# nor.net
KiCad netlist of a schematic drawn in EAGLE
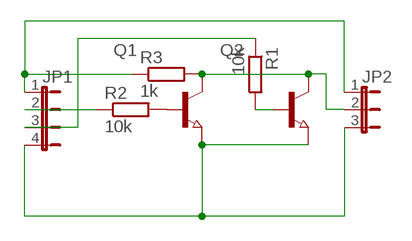
[diagram p0: schematic, sheet 1]

(export (version "E")
  (design (tool "Eeschema 10.0.6"))
  (components
    (comp (ref "JP1")
      (value "JP4E")
      (footprint "eagle-import:JP4")
      (libsource (lib "eagle-import") (part "JP4E"))
    )
    (comp (ref "JP2")
      (value "JP2W")
      (footprint "eagle-import:JP2W")
      (libsource (lib "eagle-import") (part "JP2W"))
    )
    (comp (ref "Q1")
      (value "NPN-TRANSISTOR_SOT23")
      (footprint "eagle-import:SOT23")
      (libsource (lib "eagle-import") (part "NPN-TRANSISTOR_SOT23"))
    )
    (comp (ref "Q2")
      (value "NPN-TRANSISTOR_SOT23")
      (footprint "eagle-import:SOT23")
      (libsource (lib "eagle-import") (part "NPN-TRANSISTOR_SOT23"))
    )
    (comp (ref "R1")
      (value "10k")
      (footprint "eagle-import:R1206")
      (libsource (lib "eagle-import") (part "R-EU_R1206"))
    )
    (comp (ref "R2")
      (value "10k")
      (footprint "eagle-import:R1206")
      (libsource (lib "eagle-import") (part "R-EU_R1206"))
    )
    (comp (ref "R3")
      (value "1k")
      (footprint "eagle-import:R1206")
      (libsource (lib "eagle-import") (part "R-EU_R1206"))
    )
  )
  (nets
    (net (code "1") (name "Net-(JP1-Pad1)") (class "Default")
      (node (ref "JP1") (pin "1") (pinfunction "1_1") (pintype "passive"))
      (node (ref "JP2") (pin "1") (pinfunction "1_1") (pintype "passive"))
      (node (ref "R3") (pin "1") (pinfunction "1_1") (pintype "passive"))
    )
    (net (code "2") (name "Net-(JP1-Pad2)") (class "Default")
      (node (ref "JP1") (pin "2") (pinfunction "2_2") (pintype "passive"))
      (node (ref "R2") (pin "1") (pinfunction "1_1") (pintype "passive"))
    )
    (net (code "3") (name "Net-(JP1-Pad3)") (class "Default")
      (node (ref "JP1") (pin "3") (pinfunction "3_3") (pintype "passive"))
      (node (ref "R1") (pin "1") (pinfunction "1_1") (pintype "passive"))
    )
    (net (code "4") (name "Net-(Q1-B)") (class "Default")
      (node (ref "Q1") (pin "1") (pinfunction "B_1") (pintype "passive"))
      (node (ref "R2") (pin "2") (pinfunction "2_2") (pintype "passive"))
    )
    (net (code "5") (name "Net-(Q1-C)") (class "Default")
      (node (ref "JP2") (pin "2") (pinfunction "2_2") (pintype "passive"))
      (node (ref "Q1") (pin "3") (pinfunction "C_3") (pintype "passive"))
      (node (ref "Q2") (pin "3") (pinfunction "C_3") (pintype "passive"))
      (node (ref "R3") (pin "2") (pinfunction "2_2") (pintype "passive"))
    )
    (net (code "6") (name "Net-(Q1-E)") (class "Default")
      (node (ref "JP1") (pin "4") (pinfunction "4_4") (pintype "passive"))
      (node (ref "JP2") (pin "3") (pinfunction "3_3") (pintype "passive"))
      (node (ref "Q1") (pin "2") (pinfunction "E_2") (pintype "passive"))
      (node (ref "Q2") (pin "2") (pinfunction "E_2") (pintype "passive"))
    )
    (net (code "7") (name "Net-(Q2-B)") (class "Default")
      (node (ref "Q2") (pin "1") (pinfunction "B_1") (pintype "passive"))
      (node (ref "R1") (pin "2") (pinfunction "2_2") (pintype "passive"))
    )
  )
)
